# MotorDriver.net
KiCad netlist of a schematic drawn in Altium Designer
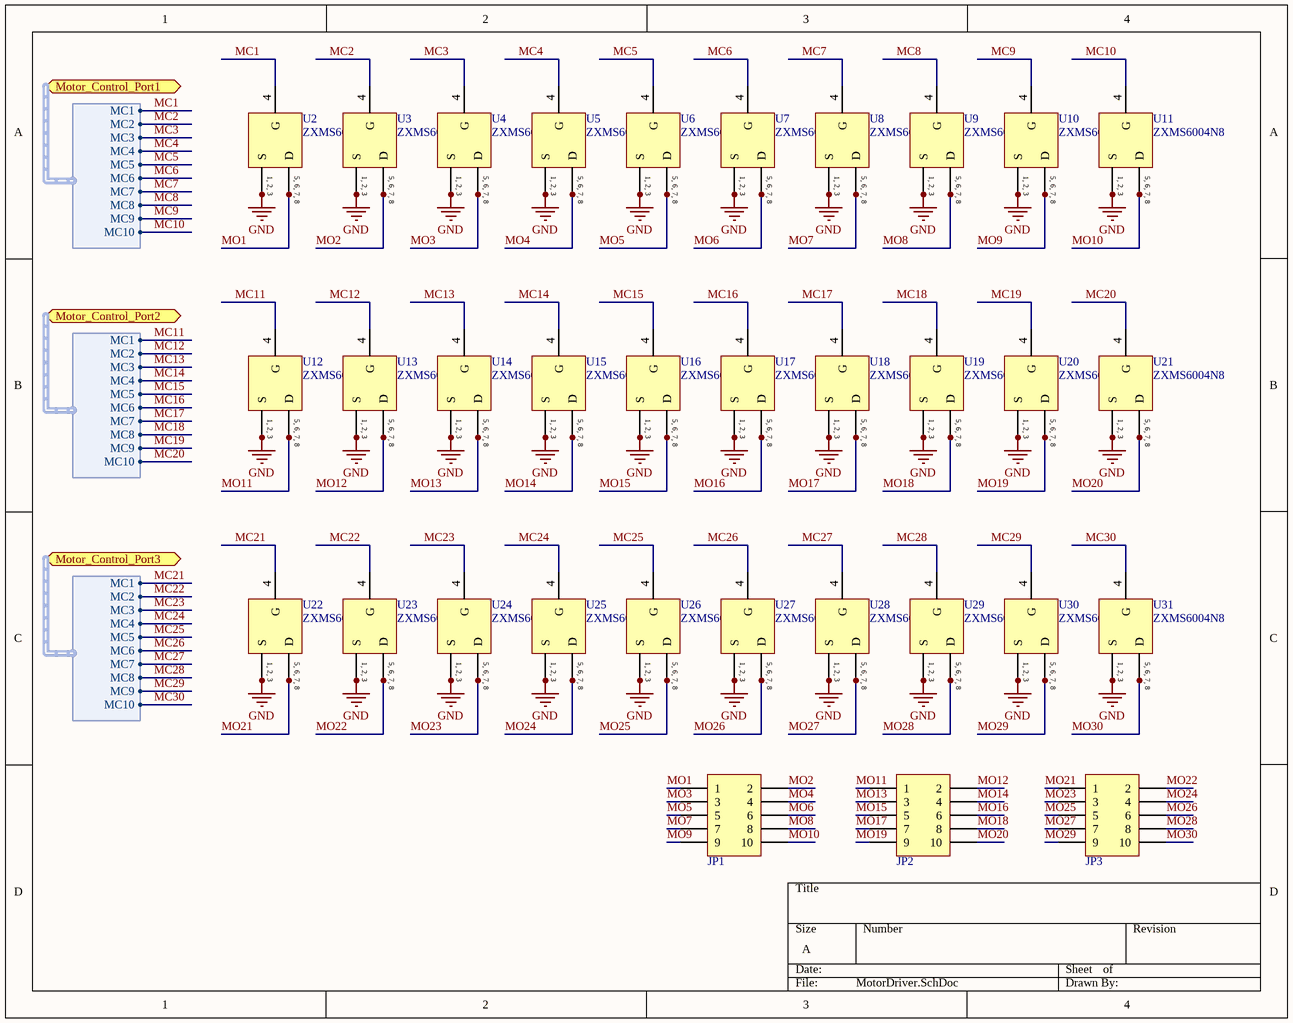
[diagram p0: MotorDriver.SchDoc]

(export (version "E")
  (design (tool "Eeschema 10.0.6"))
  (components
    (comp (ref "JP1")
      (value "Header 5x2 2.54mm")
      (footprint "2X5")
      (description "Header, 8-Pin")
      (libsource (lib "HSBNE-Vend") (part "Header 5x2"))
    )
    (comp (ref "JP2")
      (value "Header 5x2 2.54mm")
      (footprint "2X5")
      (description "Header, 8-Pin")
      (libsource (lib "HSBNE-Vend") (part "Header 5x2"))
    )
    (comp (ref "JP3")
      (value "Header 5x2 2.54mm")
      (footprint "2X5")
      (description "Header, 8-Pin")
      (libsource (lib "HSBNE-Vend") (part "Header 5x2"))
    )
    (comp (ref "U2")
      (value "ZXMS6004N8")
      (footprint "SO-8")
      (description "MOSFET N-CH 60V 1.3A S08")
      (fields (field (name "MANUFACTURER") "On Semiconductor") (field (name "PARTNUMBER") "NCV8402ASTT1G"))
      (libsource (lib "HSBNE-MAIN") (part "ZXMS6004N8"))
    )
    (comp (ref "U3")
      (value "ZXMS6004N8")
      (footprint "SO-8")
      (description "MOSFET N-CH 60V 1.3A S08")
      (fields (field (name "MANUFACTURER") "On Semiconductor") (field (name "PARTNUMBER") "NCV8402ASTT1G"))
      (libsource (lib "HSBNE-MAIN") (part "ZXMS6004N8"))
    )
    (comp (ref "U4")
      (value "ZXMS6004N8")
      (footprint "SO-8")
      (description "MOSFET N-CH 60V 1.3A S08")
      (fields (field (name "MANUFACTURER") "On Semiconductor") (field (name "PARTNUMBER") "NCV8402ASTT1G"))
      (libsource (lib "HSBNE-MAIN") (part "ZXMS6004N8"))
    )
    (comp (ref "U5")
      (value "ZXMS6004N8")
      (footprint "SO-8")
      (description "MOSFET N-CH 60V 1.3A S08")
      (fields (field (name "MANUFACTURER") "On Semiconductor") (field (name "PARTNUMBER") "NCV8402ASTT1G"))
      (libsource (lib "HSBNE-MAIN") (part "ZXMS6004N8"))
    )
    (comp (ref "U6")
      (value "ZXMS6004N8")
      (footprint "SO-8")
      (description "MOSFET N-CH 60V 1.3A S08")
      (fields (field (name "MANUFACTURER") "On Semiconductor") (field (name "PARTNUMBER") "NCV8402ASTT1G"))
      (libsource (lib "HSBNE-MAIN") (part "ZXMS6004N8"))
    )
    (comp (ref "U7")
      (value "ZXMS6004N8")
      (footprint "SO-8")
      (description "MOSFET N-CH 60V 1.3A S08")
      (fields (field (name "MANUFACTURER") "On Semiconductor") (field (name "PARTNUMBER") "NCV8402ASTT1G"))
      (libsource (lib "HSBNE-MAIN") (part "ZXMS6004N8"))
    )
    (comp (ref "U8")
      (value "ZXMS6004N8")
      (footprint "SO-8")
      (description "MOSFET N-CH 60V 1.3A S08")
      (fields (field (name "MANUFACTURER") "On Semiconductor") (field (name "PARTNUMBER") "NCV8402ASTT1G"))
      (libsource (lib "HSBNE-MAIN") (part "ZXMS6004N8"))
    )
    (comp (ref "U9")
      (value "ZXMS6004N8")
      (footprint "SO-8")
      (description "MOSFET N-CH 60V 1.3A S08")
      (fields (field (name "MANUFACTURER") "On Semiconductor") (field (name "PARTNUMBER") "NCV8402ASTT1G"))
      (libsource (lib "HSBNE-MAIN") (part "ZXMS6004N8"))
    )
    (comp (ref "U10")
      (value "ZXMS6004N8")
      (footprint "SO-8")
      (description "MOSFET N-CH 60V 1.3A S08")
      (fields (field (name "MANUFACTURER") "On Semiconductor") (field (name "PARTNUMBER") "NCV8402ASTT1G"))
      (libsource (lib "HSBNE-MAIN") (part "ZXMS6004N8"))
    )
    (comp (ref "U11")
      (value "ZXMS6004N8")
      (footprint "SO-8")
      (description "MOSFET N-CH 60V 1.3A S08")
      (fields (field (name "MANUFACTURER") "On Semiconductor") (field (name "PARTNUMBER") "NCV8402ASTT1G"))
      (libsource (lib "HSBNE-MAIN") (part "ZXMS6004N8"))
    )
    (comp (ref "U12")
      (value "ZXMS6004N8")
      (footprint "SO-8")
      (description "MOSFET N-CH 60V 1.3A S08")
      (fields (field (name "MANUFACTURER") "On Semiconductor") (field (name "PARTNUMBER") "NCV8402ASTT1G"))
      (libsource (lib "HSBNE-MAIN") (part "ZXMS6004N8"))
    )
    (comp (ref "U13")
      (value "ZXMS6004N8")
      (footprint "SO-8")
      (description "MOSFET N-CH 60V 1.3A S08")
      (fields (field (name "MANUFACTURER") "On Semiconductor") (field (name "PARTNUMBER") "NCV8402ASTT1G"))
      (libsource (lib "HSBNE-MAIN") (part "ZXMS6004N8"))
    )
    (comp (ref "U14")
      (value "ZXMS6004N8")
      (footprint "SO-8")
      (description "MOSFET N-CH 60V 1.3A S08")
      (fields (field (name "MANUFACTURER") "On Semiconductor") (field (name "PARTNUMBER") "NCV8402ASTT1G"))
      (libsource (lib "HSBNE-MAIN") (part "ZXMS6004N8"))
    )
    (comp (ref "U15")
      (value "ZXMS6004N8")
      (footprint "SO-8")
      (description "MOSFET N-CH 60V 1.3A S08")
      (fields (field (name "MANUFACTURER") "On Semiconductor") (field (name "PARTNUMBER") "NCV8402ASTT1G"))
      (libsource (lib "HSBNE-MAIN") (part "ZXMS6004N8"))
    )
    (comp (ref "U16")
      (value "ZXMS6004N8")
      (footprint "SO-8")
      (description "MOSFET N-CH 60V 1.3A S08")
      (fields (field (name "MANUFACTURER") "On Semiconductor") (field (name "PARTNUMBER") "NCV8402ASTT1G"))
      (libsource (lib "HSBNE-MAIN") (part "ZXMS6004N8"))
    )
    (comp (ref "U17")
      (value "ZXMS6004N8")
      (footprint "SO-8")
      (description "MOSFET N-CH 60V 1.3A S08")
      (fields (field (name "MANUFACTURER") "On Semiconductor") (field (name "PARTNUMBER") "NCV8402ASTT1G"))
      (libsource (lib "HSBNE-MAIN") (part "ZXMS6004N8"))
    )
    (comp (ref "U18")
      (value "ZXMS6004N8")
      (footprint "SO-8")
      (description "MOSFET N-CH 60V 1.3A S08")
      (fields (field (name "MANUFACTURER") "On Semiconductor") (field (name "PARTNUMBER") "NCV8402ASTT1G"))
      (libsource (lib "HSBNE-MAIN") (part "ZXMS6004N8"))
    )
    (comp (ref "U19")
      (value "ZXMS6004N8")
      (footprint "SO-8")
      (description "MOSFET N-CH 60V 1.3A S08")
      (fields (field (name "MANUFACTURER") "On Semiconductor") (field (name "PARTNUMBER") "NCV8402ASTT1G"))
      (libsource (lib "HSBNE-MAIN") (part "ZXMS6004N8"))
    )
    (comp (ref "U20")
      (value "ZXMS6004N8")
      (footprint "SO-8")
      (description "MOSFET N-CH 60V 1.3A S08")
      (fields (field (name "MANUFACTURER") "On Semiconductor") (field (name "PARTNUMBER") "NCV8402ASTT1G"))
      (libsource (lib "HSBNE-MAIN") (part "ZXMS6004N8"))
    )
    (comp (ref "U21")
      (value "ZXMS6004N8")
      (footprint "SO-8")
      (description "MOSFET N-CH 60V 1.3A S08")
      (fields (field (name "MANUFACTURER") "On Semiconductor") (field (name "PARTNUMBER") "NCV8402ASTT1G"))
      (libsource (lib "HSBNE-MAIN") (part "ZXMS6004N8"))
    )
    (comp (ref "U22")
      (value "ZXMS6004N8")
      (footprint "SO-8")
      (description "MOSFET N-CH 60V 1.3A S08")
      (fields (field (name "MANUFACTURER") "On Semiconductor") (field (name "PARTNUMBER") "NCV8402ASTT1G"))
      (libsource (lib "HSBNE-MAIN") (part "ZXMS6004N8"))
    )
    (comp (ref "U23")
      (value "ZXMS6004N8")
      (footprint "SO-8")
      (description "MOSFET N-CH 60V 1.3A S08")
      (fields (field (name "MANUFACTURER") "On Semiconductor") (field (name "PARTNUMBER") "NCV8402ASTT1G"))
      (libsource (lib "HSBNE-MAIN") (part "ZXMS6004N8"))
    )
    (comp (ref "U24")
      (value "ZXMS6004N8")
      (footprint "SO-8")
      (description "MOSFET N-CH 60V 1.3A S08")
      (fields (field (name "MANUFACTURER") "On Semiconductor") (field (name "PARTNUMBER") "NCV8402ASTT1G"))
      (libsource (lib "HSBNE-MAIN") (part "ZXMS6004N8"))
    )
    (comp (ref "U25")
      (value "ZXMS6004N8")
      (footprint "SO-8")
      (description "MOSFET N-CH 60V 1.3A S08")
      (fields (field (name "MANUFACTURER") "On Semiconductor") (field (name "PARTNUMBER") "NCV8402ASTT1G"))
      (libsource (lib "HSBNE-MAIN") (part "ZXMS6004N8"))
    )
    (comp (ref "U26")
      (value "ZXMS6004N8")
      (footprint "SO-8")
      (description "MOSFET N-CH 60V 1.3A S08")
      (fields (field (name "MANUFACTURER") "On Semiconductor") (field (name "PARTNUMBER") "NCV8402ASTT1G"))
      (libsource (lib "HSBNE-MAIN") (part "ZXMS6004N8"))
    )
    (comp (ref "U27")
      (value "ZXMS6004N8")
      (footprint "SO-8")
      (description "MOSFET N-CH 60V 1.3A S08")
      (fields (field (name "MANUFACTURER") "On Semiconductor") (field (name "PARTNUMBER") "NCV8402ASTT1G"))
      (libsource (lib "HSBNE-MAIN") (part "ZXMS6004N8"))
    )
    (comp (ref "U28")
      (value "ZXMS6004N8")
      (footprint "SO-8")
      (description "MOSFET N-CH 60V 1.3A S08")
      (fields (field (name "MANUFACTURER") "On Semiconductor") (field (name "PARTNUMBER") "NCV8402ASTT1G"))
      (libsource (lib "HSBNE-MAIN") (part "ZXMS6004N8"))
    )
    (comp (ref "U29")
      (value "ZXMS6004N8")
      (footprint "SO-8")
      (description "MOSFET N-CH 60V 1.3A S08")
      (fields (field (name "MANUFACTURER") "On Semiconductor") (field (name "PARTNUMBER") "NCV8402ASTT1G"))
      (libsource (lib "HSBNE-MAIN") (part "ZXMS6004N8"))
    )
    (comp (ref "U30")
      (value "ZXMS6004N8")
      (footprint "SO-8")
      (description "MOSFET N-CH 60V 1.3A S08")
      (fields (field (name "MANUFACTURER") "On Semiconductor") (field (name "PARTNUMBER") "NCV8402ASTT1G"))
      (libsource (lib "HSBNE-MAIN") (part "ZXMS6004N8"))
    )
    (comp (ref "U31")
      (value "ZXMS6004N8")
      (footprint "SO-8")
      (description "MOSFET N-CH 60V 1.3A S08")
      (fields (field (name "MANUFACTURER") "On Semiconductor") (field (name "PARTNUMBER") "NCV8402ASTT1G"))
      (libsource (lib "HSBNE-MAIN") (part "ZXMS6004N8"))
    )
  )
  (nets
    (net (code "2") (name "/MC1") (class "Default")
      (node (ref "U2") (pin "4") (pinfunction "G_4") (pintype "passive"))
    )
    (net (code "3") (name "/MC2") (class "Default")
      (node (ref "U3") (pin "4") (pinfunction "G_4") (pintype "passive"))
    )
    (net (code "4") (name "/MC3") (class "Default")
      (node (ref "U4") (pin "4") (pinfunction "G_4") (pintype "passive"))
    )
    (net (code "5") (name "/MC4") (class "Default")
      (node (ref "U5") (pin "4") (pinfunction "G_4") (pintype "passive"))
    )
    (net (code "6") (name "/MC5") (class "Default")
      (node (ref "U6") (pin "4") (pinfunction "G_4") (pintype "passive"))
    )
    (net (code "7") (name "/MC6") (class "Default")
      (node (ref "U7") (pin "4") (pinfunction "G_4") (pintype "passive"))
    )
    (net (code "8") (name "/MC7") (class "Default")
      (node (ref "U8") (pin "4") (pinfunction "G_4") (pintype "passive"))
    )
    (net (code "9") (name "/MC8") (class "Default")
      (node (ref "U9") (pin "4") (pinfunction "G_4") (pintype "passive"))
    )
    (net (code "10") (name "/MC9") (class "Default")
      (node (ref "U10") (pin "4") (pinfunction "G_4") (pintype "passive"))
    )
    (net (code "11") (name "/MC10") (class "Default")
      (node (ref "U11") (pin "4") (pinfunction "G_4") (pintype "passive"))
    )
    (net (code "12") (name "/MC11") (class "Default")
      (node (ref "U12") (pin "4") (pinfunction "G_4") (pintype "passive"))
    )
    (net (code "13") (name "/MC12") (class "Default")
      (node (ref "U13") (pin "4") (pinfunction "G_4") (pintype "passive"))
    )
    (net (code "14") (name "/MC13") (class "Default")
      (node (ref "U14") (pin "4") (pinfunction "G_4") (pintype "passive"))
    )
    (net (code "15") (name "/MC14") (class "Default")
      (node (ref "U15") (pin "4") (pinfunction "G_4") (pintype "passive"))
    )
    (net (code "16") (name "/MC15") (class "Default")
      (node (ref "U16") (pin "4") (pinfunction "G_4") (pintype "passive"))
    )
    (net (code "17") (name "/MC16") (class "Default")
      (node (ref "U17") (pin "4") (pinfunction "G_4") (pintype "passive"))
    )
    (net (code "18") (name "/MC17") (class "Default")
      (node (ref "U18") (pin "4") (pinfunction "G_4") (pintype "passive"))
    )
    (net (code "19") (name "/MC18") (class "Default")
      (node (ref "U19") (pin "4") (pinfunction "G_4") (pintype "passive"))
    )
    (net (code "20") (name "/MC19") (class "Default")
      (node (ref "U20") (pin "4") (pinfunction "G_4") (pintype "passive"))
    )
    (net (code "21") (name "/MC20") (class "Default")
      (node (ref "U21") (pin "4") (pinfunction "G_4") (pintype "passive"))
    )
    (net (code "22") (name "/MC21") (class "Default")
      (node (ref "U22") (pin "4") (pinfunction "G_4") (pintype "passive"))
    )
    (net (code "23") (name "/MC22") (class "Default")
      (node (ref "U23") (pin "4") (pinfunction "G_4") (pintype "passive"))
    )
    (net (code "24") (name "/MC23") (class "Default")
      (node (ref "U24") (pin "4") (pinfunction "G_4") (pintype "passive"))
    )
    (net (code "25") (name "/MC24") (class "Default")
      (node (ref "U25") (pin "4") (pinfunction "G_4") (pintype "passive"))
    )
    (net (code "26") (name "/MC25") (class "Default")
      (node (ref "U26") (pin "4") (pinfunction "G_4") (pintype "passive"))
    )
    (net (code "27") (name "/MC26") (class "Default")
      (node (ref "U27") (pin "4") (pinfunction "G_4") (pintype "passive"))
    )
    (net (code "28") (name "/MC27") (class "Default")
      (node (ref "U28") (pin "4") (pinfunction "G_4") (pintype "passive"))
    )
    (net (code "29") (name "/MC28") (class "Default")
      (node (ref "U29") (pin "4") (pinfunction "G_4") (pintype "passive"))
    )
    (net (code "30") (name "/MC29") (class "Default")
      (node (ref "U30") (pin "4") (pinfunction "G_4") (pintype "passive"))
    )
    (net (code "31") (name "/MC30") (class "Default")
      (node (ref "U31") (pin "4") (pinfunction "G_4") (pintype "passive"))
    )
    (net (code "32") (name "/MO1") (class "Default")
      (node (ref "JP1") (pin "1") (pinfunction "1_1") (pintype "passive"))
      (node (ref "U2") (pin "5") (pinfunction "D_5") (pintype "passive"))
      (node (ref "U2") (pin "6") (pinfunction "D_6") (pintype "passive"))
      (node (ref "U2") (pin "7") (pinfunction "D_7") (pintype "passive"))
      (node (ref "U2") (pin "8") (pinfunction "D_8") (pintype "passive"))
    )
    (net (code "33") (name "/MO2") (class "Default")
      (node (ref "JP1") (pin "2") (pinfunction "2_2") (pintype "passive"))
      (node (ref "U3") (pin "5") (pinfunction "D_5") (pintype "passive"))
      (node (ref "U3") (pin "6") (pinfunction "D_6") (pintype "passive"))
      (node (ref "U3") (pin "7") (pinfunction "D_7") (pintype "passive"))
      (node (ref "U3") (pin "8") (pinfunction "D_8") (pintype "passive"))
    )
    (net (code "34") (name "/MO3") (class "Default")
      (node (ref "JP1") (pin "3") (pinfunction "3_3") (pintype "passive"))
      (node (ref "U4") (pin "5") (pinfunction "D_5") (pintype "passive"))
      (node (ref "U4") (pin "6") (pinfunction "D_6") (pintype "passive"))
      (node (ref "U4") (pin "7") (pinfunction "D_7") (pintype "passive"))
      (node (ref "U4") (pin "8") (pinfunction "D_8") (pintype "passive"))
    )
    (net (code "35") (name "/MO4") (class "Default")
      (node (ref "JP1") (pin "4") (pinfunction "4_4") (pintype "passive"))
      (node (ref "U5") (pin "5") (pinfunction "D_5") (pintype "passive"))
      (node (ref "U5") (pin "6") (pinfunction "D_6") (pintype "passive"))
      (node (ref "U5") (pin "7") (pinfunction "D_7") (pintype "passive"))
      (node (ref "U5") (pin "8") (pinfunction "D_8") (pintype "passive"))
    )
    (net (code "36") (name "/MO5") (class "Default")
      (node (ref "JP1") (pin "5") (pinfunction "5_5") (pintype "passive"))
      (node (ref "U6") (pin "5") (pinfunction "D_5") (pintype "passive"))
      (node (ref "U6") (pin "6") (pinfunction "D_6") (pintype "passive"))
      (node (ref "U6") (pin "7") (pinfunction "D_7") (pintype "passive"))
      (node (ref "U6") (pin "8") (pinfunction "D_8") (pintype "passive"))
    )
    (net (code "37") (name "/MO6") (class "Default")
      (node (ref "JP1") (pin "6") (pinfunction "6_6") (pintype "passive"))
      (node (ref "U7") (pin "5") (pinfunction "D_5") (pintype "passive"))
      (node (ref "U7") (pin "6") (pinfunction "D_6") (pintype "passive"))
      (node (ref "U7") (pin "7") (pinfunction "D_7") (pintype "passive"))
      (node (ref "U7") (pin "8") (pinfunction "D_8") (pintype "passive"))
    )
    (net (code "38") (name "/MO7") (class "Default")
      (node (ref "JP1") (pin "7") (pinfunction "7_7") (pintype "passive"))
      (node (ref "U8") (pin "5") (pinfunction "D_5") (pintype "passive"))
      (node (ref "U8") (pin "6") (pinfunction "D_6") (pintype "passive"))
      (node (ref "U8") (pin "7") (pinfunction "D_7") (pintype "passive"))
      (node (ref "U8") (pin "8") (pinfunction "D_8") (pintype "passive"))
    )
    (net (code "39") (name "/MO8") (class "Default")
      (node (ref "JP1") (pin "8") (pinfunction "8_8") (pintype "passive"))
      (node (ref "U9") (pin "5") (pinfunction "D_5") (pintype "passive"))
      (node (ref "U9") (pin "6") (pinfunction "D_6") (pintype "passive"))
      (node (ref "U9") (pin "7") (pinfunction "D_7") (pintype "passive"))
      (node (ref "U9") (pin "8") (pinfunction "D_8") (pintype "passive"))
    )
    (net (code "40") (name "/MO9") (class "Default")
      (node (ref "JP1") (pin "9") (pinfunction "9_9") (pintype "passive"))
      (node (ref "U10") (pin "5") (pinfunction "D_5") (pintype "passive"))
      (node (ref "U10") (pin "6") (pinfunction "D_6") (pintype "passive"))
      (node (ref "U10") (pin "7") (pinfunction "D_7") (pintype "passive"))
      (node (ref "U10") (pin "8") (pinfunction "D_8") (pintype "passive"))
    )
    (net (code "41") (name "/MO10") (class "Default")
      (node (ref "JP1") (pin "10") (pinfunction "10_10") (pintype "passive"))
      (node (ref "U11") (pin "5") (pinfunction "D_5") (pintype "passive"))
      (node (ref "U11") (pin "6") (pinfunction "D_6") (pintype "passive"))
      (node (ref "U11") (pin "7") (pinfunction "D_7") (pintype "passive"))
      (node (ref "U11") (pin "8") (pinfunction "D_8") (pintype "passive"))
    )
    (net (code "42") (name "/MO11") (class "Default")
      (node (ref "JP2") (pin "1") (pinfunction "1_1") (pintype "passive"))
      (node (ref "U12") (pin "5") (pinfunction "D_5") (pintype "passive"))
      (node (ref "U12") (pin "6") (pinfunction "D_6") (pintype "passive"))
      (node (ref "U12") (pin "7") (pinfunction "D_7") (pintype "passive"))
      (node (ref "U12") (pin "8") (pinfunction "D_8") (pintype "passive"))
    )
    (net (code "43") (name "/MO12") (class "Default")
      (node (ref "JP2") (pin "2") (pinfunction "2_2") (pintype "passive"))
      (node (ref "U13") (pin "5") (pinfunction "D_5") (pintype "passive"))
      (node (ref "U13") (pin "6") (pinfunction "D_6") (pintype "passive"))
      (node (ref "U13") (pin "7") (pinfunction "D_7") (pintype "passive"))
      (node (ref "U13") (pin "8") (pinfunction "D_8") (pintype "passive"))
    )
    (net (code "44") (name "/MO13") (class "Default")
      (node (ref "JP2") (pin "3") (pinfunction "3_3") (pintype "passive"))
      (node (ref "U14") (pin "5") (pinfunction "D_5") (pintype "passive"))
      (node (ref "U14") (pin "6") (pinfunction "D_6") (pintype "passive"))
      (node (ref "U14") (pin "7") (pinfunction "D_7") (pintype "passive"))
      (node (ref "U14") (pin "8") (pinfunction "D_8") (pintype "passive"))
    )
    (net (code "45") (name "/MO14") (class "Default")
      (node (ref "JP2") (pin "4") (pinfunction "4_4") (pintype "passive"))
      (node (ref "U15") (pin "5") (pinfunction "D_5") (pintype "passive"))
      (node (ref "U15") (pin "6") (pinfunction "D_6") (pintype "passive"))
      (node (ref "U15") (pin "7") (pinfunction "D_7") (pintype "passive"))
      (node (ref "U15") (pin "8") (pinfunction "D_8") (pintype "passive"))
    )
    (net (code "46") (name "/MO15") (class "Default")
      (node (ref "JP2") (pin "5") (pinfunction "5_5") (pintype "passive"))
      (node (ref "U16") (pin "5") (pinfunction "D_5") (pintype "passive"))
      (node (ref "U16") (pin "6") (pinfunction "D_6") (pintype "passive"))
      (node (ref "U16") (pin "7") (pinfunction "D_7") (pintype "passive"))
      (node (ref "U16") (pin "8") (pinfunction "D_8") (pintype "passive"))
    )
    (net (code "47") (name "/MO16") (class "Default")
      (node (ref "JP2") (pin "6") (pinfunction "6_6") (pintype "passive"))
      (node (ref "U17") (pin "5") (pinfunction "D_5") (pintype "passive"))
      (node (ref "U17") (pin "6") (pinfunction "D_6") (pintype "passive"))
      (node (ref "U17") (pin "7") (pinfunction "D_7") (pintype "passive"))
      (node (ref "U17") (pin "8") (pinfunction "D_8") (pintype "passive"))
    )
    (net (code "48") (name "/MO17") (class "Default")
      (node (ref "JP2") (pin "7") (pinfunction "7_7") (pintype "passive"))
      (node (ref "U18") (pin "5") (pinfunction "D_5") (pintype "passive"))
      (node (ref "U18") (pin "6") (pinfunction "D_6") (pintype "passive"))
      (node (ref "U18") (pin "7") (pinfunction "D_7") (pintype "passive"))
      (node (ref "U18") (pin "8") (pinfunction "D_8") (pintype "passive"))
    )
    (net (code "49") (name "/MO18") (class "Default")
      (node (ref "JP2") (pin "8") (pinfunction "8_8") (pintype "passive"))
      (node (ref "U19") (pin "5") (pinfunction "D_5") (pintype "passive"))
      (node (ref "U19") (pin "6") (pinfunction "D_6") (pintype "passive"))
      (node (ref "U19") (pin "7") (pinfunction "D_7") (pintype "passive"))
      (node (ref "U19") (pin "8") (pinfunction "D_8") (pintype "passive"))
    )
    (net (code "50") (name "/MO19") (class "Default")
      (node (ref "JP2") (pin "9") (pinfunction "9_9") (pintype "passive"))
      (node (ref "U20") (pin "5") (pinfunction "D_5") (pintype "passive"))
      (node (ref "U20") (pin "6") (pinfunction "D_6") (pintype "passive"))
      (node (ref "U20") (pin "7") (pinfunction "D_7") (pintype "passive"))
      (node (ref "U20") (pin "8") (pinfunction "D_8") (pintype "passive"))
    )
    (net (code "51") (name "/MO20") (class "Default")
      (node (ref "JP2") (pin "10") (pinfunction "10_10") (pintype "passive"))
      (node (ref "U21") (pin "5") (pinfunction "D_5") (pintype "passive"))
      (node (ref "U21") (pin "6") (pinfunction "D_6") (pintype "passive"))
      (node (ref "U21") (pin "7") (pinfunction "D_7") (pintype "passive"))
      (node (ref "U21") (pin "8") (pinfunction "D_8") (pintype "passive"))
    )
    (net (code "52") (name "/MO21") (class "Default")
      (node (ref "JP3") (pin "1") (pinfunction "1_1") (pintype "passive"))
      (node (ref "U22") (pin "5") (pinfunction "D_5") (pintype "passive"))
      (node (ref "U22") (pin "6") (pinfunction "D_6") (pintype "passive"))
      (node (ref "U22") (pin "7") (pinfunction "D_7") (pintype "passive"))
      (node (ref "U22") (pin "8") (pinfunction "D_8") (pintype "passive"))
    )
    (net (code "53") (name "/MO22") (class "Default")
      (node (ref "JP3") (pin "2") (pinfunction "2_2") (pintype "passive"))
      (node (ref "U23") (pin "5") (pinfunction "D_5") (pintype "passive"))
      (node (ref "U23") (pin "6") (pinfunction "D_6") (pintype "passive"))
      (node (ref "U23") (pin "7") (pinfunction "D_7") (pintype "passive"))
      (node (ref "U23") (pin "8") (pinfunction "D_8") (pintype "passive"))
    )
    (net (code "54") (name "/MO23") (class "Default")
      (node (ref "JP3") (pin "3") (pinfunction "3_3") (pintype "passive"))
      (node (ref "U24") (pin "5") (pinfunction "D_5") (pintype "passive"))
      (node (ref "U24") (pin "6") (pinfunction "D_6") (pintype "passive"))
      (node (ref "U24") (pin "7") (pinfunction "D_7") (pintype "passive"))
      (node (ref "U24") (pin "8") (pinfunction "D_8") (pintype "passive"))
    )
    (net (code "55") (name "/MO24") (class "Default")
      (node (ref "JP3") (pin "4") (pinfunction "4_4") (pintype "passive"))
      (node (ref "U25") (pin "5") (pinfunction "D_5") (pintype "passive"))
      (node (ref "U25") (pin "6") (pinfunction "D_6") (pintype "passive"))
      (node (ref "U25") (pin "7") (pinfunction "D_7") (pintype "passive"))
      (node (ref "U25") (pin "8") (pinfunction "D_8") (pintype "passive"))
    )
    (net (code "56") (name "/MO25") (class "Default")
      (node (ref "JP3") (pin "5") (pinfunction "5_5") (pintype "passive"))
      (node (ref "U26") (pin "5") (pinfunction "D_5") (pintype "passive"))
      (node (ref "U26") (pin "6") (pinfunction "D_6") (pintype "passive"))
      (node (ref "U26") (pin "7") (pinfunction "D_7") (pintype "passive"))
      (node (ref "U26") (pin "8") (pinfunction "D_8") (pintype "passive"))
    )
    (net (code "57") (name "/MO26") (class "Default")
      (node (ref "JP3") (pin "6") (pinfunction "6_6") (pintype "passive"))
      (node (ref "U27") (pin "5") (pinfunction "D_5") (pintype "passive"))
      (node (ref "U27") (pin "6") (pinfunction "D_6") (pintype "passive"))
      (node (ref "U27") (pin "7") (pinfunction "D_7") (pintype "passive"))
      (node (ref "U27") (pin "8") (pinfunction "D_8") (pintype "passive"))
    )
    (net (code "58") (name "/MO27") (class "Default")
      (node (ref "JP3") (pin "7") (pinfunction "7_7") (pintype "passive"))
      (node (ref "U28") (pin "5") (pinfunction "D_5") (pintype "passive"))
      (node (ref "U28") (pin "6") (pinfunction "D_6") (pintype "passive"))
      (node (ref "U28") (pin "7") (pinfunction "D_7") (pintype "passive"))
      (node (ref "U28") (pin "8") (pinfunction "D_8") (pintype "passive"))
    )
    (net (code "59") (name "/MO28") (class "Default")
      (node (ref "JP3") (pin "8") (pinfunction "8_8") (pintype "passive"))
      (node (ref "U29") (pin "5") (pinfunction "D_5") (pintype "passive"))
      (node (ref "U29") (pin "6") (pinfunction "D_6") (pintype "passive"))
      (node (ref "U29") (pin "7") (pinfunction "D_7") (pintype "passive"))
      (node (ref "U29") (pin "8") (pinfunction "D_8") (pintype "passive"))
    )
    (net (code "60") (name "/MO29") (class "Default")
      (node (ref "JP3") (pin "9") (pinfunction "9_9") (pintype "passive"))
      (node (ref "U30") (pin "5") (pinfunction "D_5") (pintype "passive"))
      (node (ref "U30") (pin "6") (pinfunction "D_6") (pintype "passive"))
      (node (ref "U30") (pin "7") (pinfunction "D_7") (pintype "passive"))
      (node (ref "U30") (pin "8") (pinfunction "D_8") (pintype "passive"))
    )
    (net (code "61") (name "/MO30") (class "Default")
      (node (ref "JP3") (pin "10") (pinfunction "10_10") (pintype "passive"))
      (node (ref "U31") (pin "5") (pinfunction "D_5") (pintype "passive"))
      (node (ref "U31") (pin "6") (pinfunction "D_6") (pintype "passive"))
      (node (ref "U31") (pin "7") (pinfunction "D_7") (pintype "passive"))
      (node (ref "U31") (pin "8") (pinfunction "D_8") (pintype "passive"))
    )
    (net (code "63") (name "GND") (class "Default")
      (node (ref "U10") (pin "1") (pinfunction "S_1") (pintype "passive"))
      (node (ref "U10") (pin "2") (pinfunction "S_2") (pintype "passive"))
      (node (ref "U10") (pin "3") (pinfunction "S_3") (pintype "passive"))
      (node (ref "U11") (pin "1") (pinfunction "S_1") (pintype "passive"))
      (node (ref "U11") (pin "2") (pinfunction "S_2") (pintype "passive"))
      (node (ref "U11") (pin "3") (pinfunction "S_3") (pintype "passive"))
      (node (ref "U12") (pin "1") (pinfunction "S_1") (pintype "passive"))
      (node (ref "U12") (pin "2") (pinfunction "S_2") (pintype "passive"))
      (node (ref "U12") (pin "3") (pinfunction "S_3") (pintype "passive"))
      (node (ref "U13") (pin "1") (pinfunction "S_1") (pintype "passive"))
      (node (ref "U13") (pin "2") (pinfunction "S_2") (pintype "passive"))
      (node (ref "U13") (pin "3") (pinfunction "S_3") (pintype "passive"))
      (node (ref "U14") (pin "1") (pinfunction "S_1") (pintype "passive"))
      (node (ref "U14") (pin "2") (pinfunction "S_2") (pintype "passive"))
      (node (ref "U14") (pin "3") (pinfunction "S_3") (pintype "passive"))
      (node (ref "U15") (pin "1") (pinfunction "S_1") (pintype "passive"))
      (node (ref "U15") (pin "2") (pinfunction "S_2") (pintype "passive"))
      (node (ref "U15") (pin "3") (pinfunction "S_3") (pintype "passive"))
      (node (ref "U16") (pin "1") (pinfunction "S_1") (pintype "passive"))
      (node (ref "U16") (pin "2") (pinfunction "S_2") (pintype "passive"))
      (node (ref "U16") (pin "3") (pinfunction "S_3") (pintype "passive"))
      (node (ref "U17") (pin "1") (pinfunction "S_1") (pintype "passive"))
      (node (ref "U17") (pin "2") (pinfunction "S_2") (pintype "passive"))
      (node (ref "U17") (pin "3") (pinfunction "S_3") (pintype "passive"))
      (node (ref "U18") (pin "1") (pinfunction "S_1") (pintype "passive"))
      (node (ref "U18") (pin "2") (pinfunction "S_2") (pintype "passive"))
      (node (ref "U18") (pin "3") (pinfunction "S_3") (pintype "passive"))
      (node (ref "U19") (pin "1") (pinfunction "S_1") (pintype "passive"))
      (node (ref "U19") (pin "2") (pinfunction "S_2") (pintype "passive"))
      (node (ref "U19") (pin "3") (pinfunction "S_3") (pintype "passive"))
      (node (ref "U2") (pin "1") (pinfunction "S_1") (pintype "passive"))
      (node (ref "U2") (pin "2") (pinfunction "S_2") (pintype "passive"))
      (node (ref "U2") (pin "3") (pinfunction "S_3") (pintype "passive"))
      (node (ref "U20") (pin "1") (pinfunction "S_1") (pintype "passive"))
      (node (ref "U20") (pin "2") (pinfunction "S_2") (pintype "passive"))
      (node (ref "U20") (pin "3") (pinfunction "S_3") (pintype "passive"))
      (node (ref "U21") (pin "1") (pinfunction "S_1") (pintype "passive"))
      (node (ref "U21") (pin "2") (pinfunction "S_2") (pintype "passive"))
      (node (ref "U21") (pin "3") (pinfunction "S_3") (pintype "passive"))
      (node (ref "U22") (pin "1") (pinfunction "S_1") (pintype "passive"))
      (node (ref "U22") (pin "2") (pinfunction "S_2") (pintype "passive"))
      (node (ref "U22") (pin "3") (pinfunction "S_3") (pintype "passive"))
      (node (ref "U23") (pin "1") (pinfunction "S_1") (pintype "passive"))
      (node (ref "U23") (pin "2") (pinfunction "S_2") (pintype "passive"))
      (node (ref "U23") (pin "3") (pinfunction "S_3") (pintype "passive"))
      (node (ref "U24") (pin "1") (pinfunction "S_1") (pintype "passive"))
      (node (ref "U24") (pin "2") (pinfunction "S_2") (pintype "passive"))
      (node (ref "U24") (pin "3") (pinfunction "S_3") (pintype "passive"))
      (node (ref "U25") (pin "1") (pinfunction "S_1") (pintype "passive"))
      (node (ref "U25") (pin "2") (pinfunction "S_2") (pintype "passive"))
      (node (ref "U25") (pin "3") (pinfunction "S_3") (pintype "passive"))
      (node (ref "U26") (pin "1") (pinfunction "S_1") (pintype "passive"))
      (node (ref "U26") (pin "2") (pinfunction "S_2") (pintype "passive"))
      (node (ref "U26") (pin "3") (pinfunction "S_3") (pintype "passive"))
      (node (ref "U27") (pin "1") (pinfunction "S_1") (pintype "passive"))
      (node (ref "U27") (pin "2") (pinfunction "S_2") (pintype "passive"))
      (node (ref "U27") (pin "3") (pinfunction "S_3") (pintype "passive"))
      (node (ref "U28") (pin "1") (pinfunction "S_1") (pintype "passive"))
      (node (ref "U28") (pin "2") (pinfunction "S_2") (pintype "passive"))
      (node (ref "U28") (pin "3") (pinfunction "S_3") (pintype "passive"))
      (node (ref "U29") (pin "1") (pinfunction "S_1") (pintype "passive"))
      (node (ref "U29") (pin "2") (pinfunction "S_2") (pintype "passive"))
      (node (ref "U29") (pin "3") (pinfunction "S_3") (pintype "passive"))
      (node (ref "U3") (pin "1") (pinfunction "S_1") (pintype "passive"))
      (node (ref "U3") (pin "2") (pinfunction "S_2") (pintype "passive"))
      (node (ref "U3") (pin "3") (pinfunction "S_3") (pintype "passive"))
      (node (ref "U30") (pin "1") (pinfunction "S_1") (pintype "passive"))
      (node (ref "U30") (pin "2") (pinfunction "S_2") (pintype "passive"))
      (node (ref "U30") (pin "3") (pinfunction "S_3") (pintype "passive"))
      (node (ref "U31") (pin "1") (pinfunction "S_1") (pintype "passive"))
      (node (ref "U31") (pin "2") (pinfunction "S_2") (pintype "passive"))
      (node (ref "U31") (pin "3") (pinfunction "S_3") (pintype "passive"))
      (node (ref "U4") (pin "1") (pinfunction "S_1") (pintype "passive"))
      (node (ref "U4") (pin "2") (pinfunction "S_2") (pintype "passive"))
      (node (ref "U4") (pin "3") (pinfunction "S_3") (pintype "passive"))
      (node (ref "U5") (pin "1") (pinfunction "S_1") (pintype "passive"))
      (node (ref "U5") (pin "2") (pinfunction "S_2") (pintype "passive"))
      (node (ref "U5") (pin "3") (pinfunction "S_3") (pintype "passive"))
      (node (ref "U6") (pin "1") (pinfunction "S_1") (pintype "passive"))
      (node (ref "U6") (pin "2") (pinfunction "S_2") (pintype "passive"))
      (node (ref "U6") (pin "3") (pinfunction "S_3") (pintype "passive"))
      (node (ref "U7") (pin "1") (pinfunction "S_1") (pintype "passive"))
      (node (ref "U7") (pin "2") (pinfunction "S_2") (pintype "passive"))
      (node (ref "U7") (pin "3") (pinfunction "S_3") (pintype "passive"))
      (node (ref "U8") (pin "1") (pinfunction "S_1") (pintype "passive"))
      (node (ref "U8") (pin "2") (pinfunction "S_2") (pintype "passive"))
      (node (ref "U8") (pin "3") (pinfunction "S_3") (pintype "passive"))
      (node (ref "U9") (pin "1") (pinfunction "S_1") (pintype "passive"))
      (node (ref "U9") (pin "2") (pinfunction "S_2") (pintype "passive"))
      (node (ref "U9") (pin "3") (pinfunction "S_3") (pintype "passive"))
    )
  )
)
